# W101B.net
KiCad netlist of a schematic drawn in EAGLE
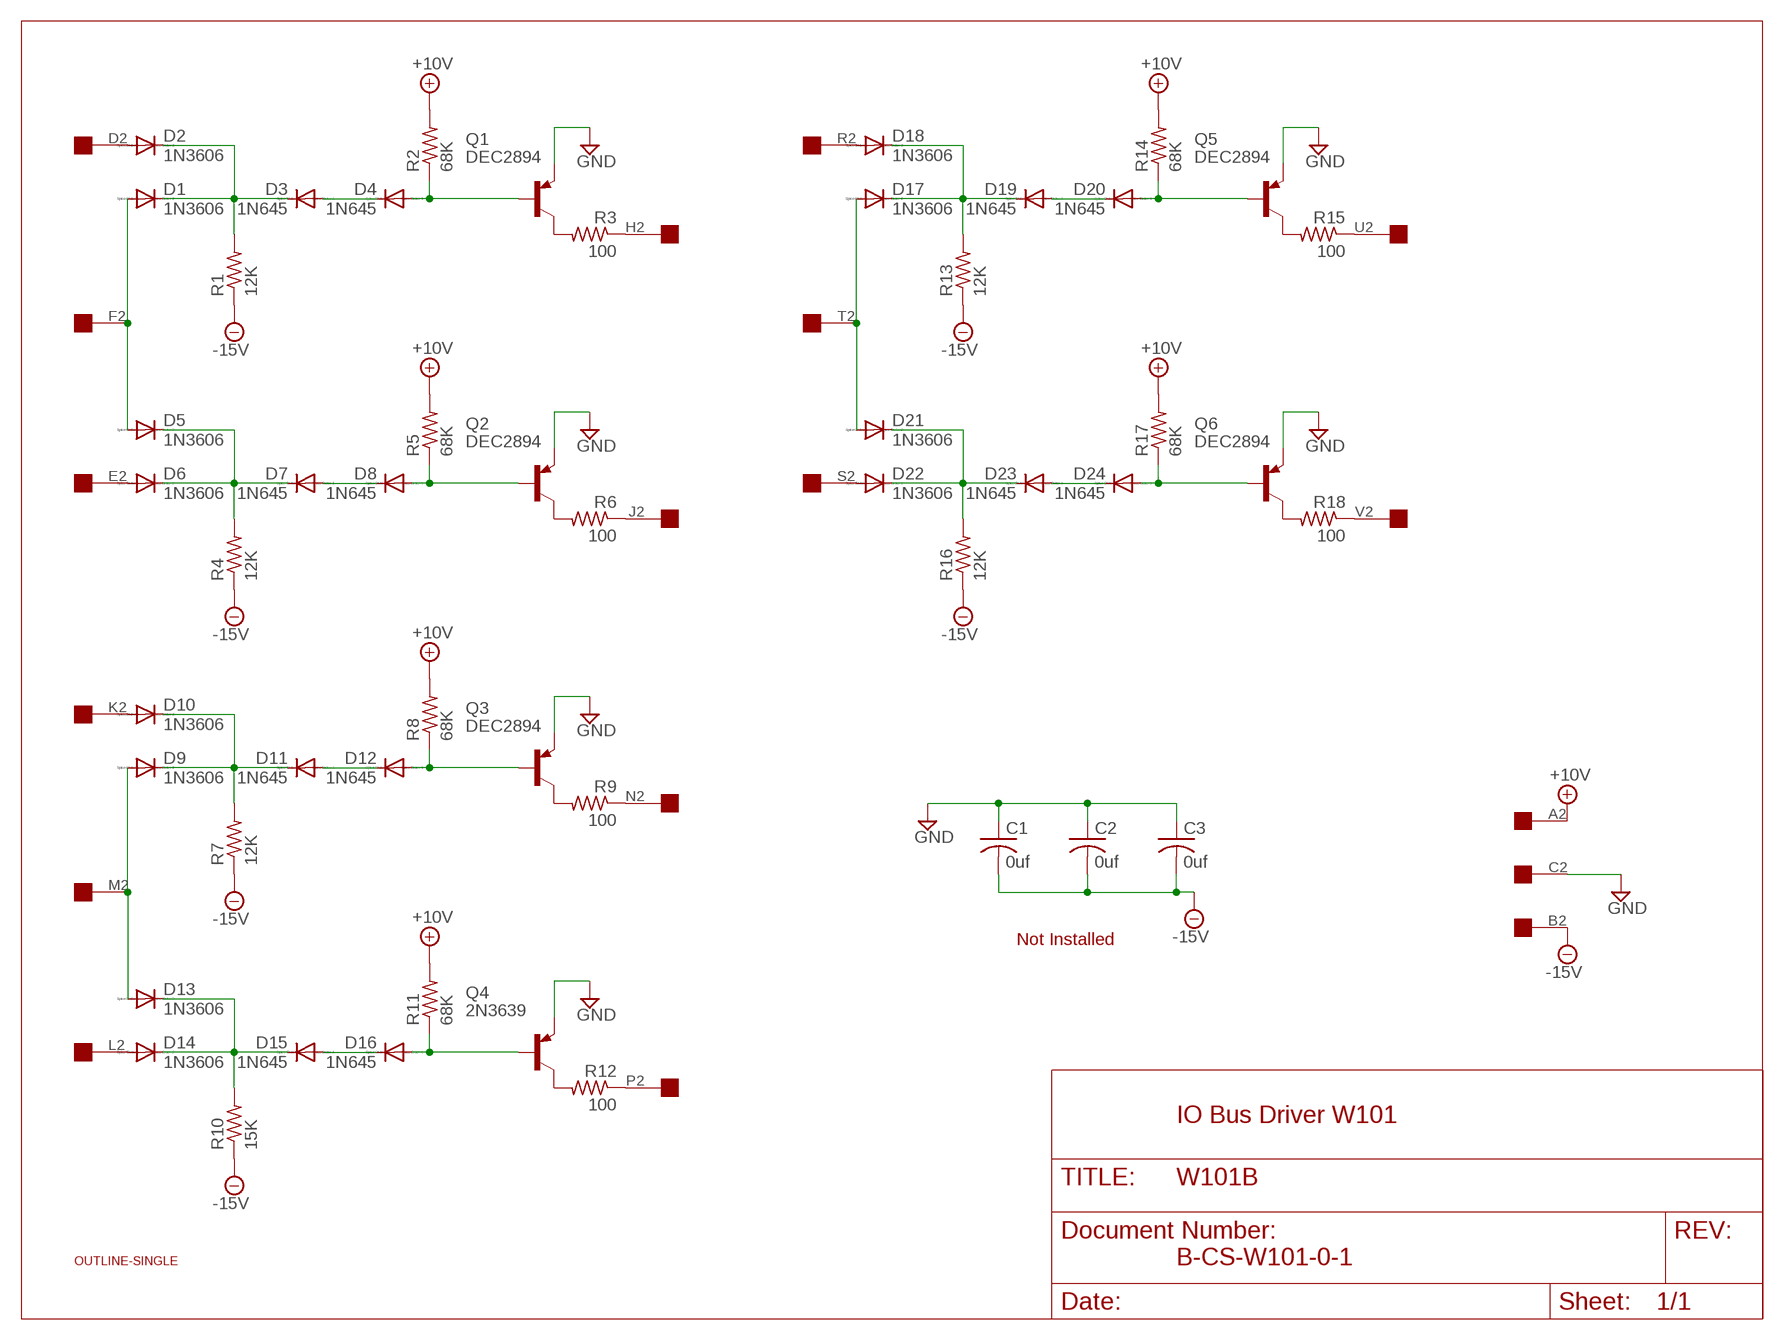
[diagram p0: schematic, sheet 1]

(export (version "E")
  (design (tool "Eeschema 10.0.6"))
  (components
    (comp (ref "C1")
      (value "0uf")
      (footprint "eagle-import:C050-025X075")
      (libsource (lib "eagle-import") (part "C-US050-025X075"))
    )
    (comp (ref "C2")
      (value "0uf")
      (footprint "eagle-import:C050-025X075")
      (libsource (lib "eagle-import") (part "C-US050-025X075"))
    )
    (comp (ref "C3")
      (value "0uf")
      (footprint "eagle-import:C050-025X075")
      (libsource (lib "eagle-import") (part "C-US050-025X075"))
    )
    (comp (ref "D1")
      (value "1N3606")
      (footprint "eagle-import:DO35-10")
      (libsource (lib "eagle-import") (part "1N4148DO35-10"))
    )
    (comp (ref "D2")
      (value "1N3606")
      (footprint "eagle-import:DO35-10")
      (libsource (lib "eagle-import") (part "1N4148DO35-10"))
    )
    (comp (ref "D3")
      (value "1N645")
      (footprint "eagle-import:DO35-10")
      (libsource (lib "eagle-import") (part "1N4148DO35-10"))
    )
    (comp (ref "D4")
      (value "1N645")
      (footprint "eagle-import:DO35-10")
      (libsource (lib "eagle-import") (part "1N4148DO35-10"))
    )
    (comp (ref "D5")
      (value "1N3606")
      (footprint "eagle-import:DO35-10")
      (libsource (lib "eagle-import") (part "1N4148DO35-10"))
    )
    (comp (ref "D6")
      (value "1N3606")
      (footprint "eagle-import:DO35-10")
      (libsource (lib "eagle-import") (part "1N4148DO35-10"))
    )
    (comp (ref "D7")
      (value "1N645")
      (footprint "eagle-import:DO35-10")
      (libsource (lib "eagle-import") (part "1N4148DO35-10"))
    )
    (comp (ref "D8")
      (value "1N645")
      (footprint "eagle-import:DO35-10")
      (libsource (lib "eagle-import") (part "1N4148DO35-10"))
    )
    (comp (ref "D9")
      (value "1N3606")
      (footprint "eagle-import:DO35-10")
      (libsource (lib "eagle-import") (part "1N4148DO35-10"))
    )
    (comp (ref "D10")
      (value "1N3606")
      (footprint "eagle-import:DO35-10")
      (libsource (lib "eagle-import") (part "1N4148DO35-10"))
    )
    (comp (ref "D11")
      (value "1N645")
      (footprint "eagle-import:DO35-10")
      (libsource (lib "eagle-import") (part "1N4148DO35-10"))
    )
    (comp (ref "D12")
      (value "1N645")
      (footprint "eagle-import:DO35-10")
      (libsource (lib "eagle-import") (part "1N4148DO35-10"))
    )
    (comp (ref "D13")
      (value "1N3606")
      (footprint "eagle-import:DO35-10")
      (libsource (lib "eagle-import") (part "1N4148DO35-10"))
    )
    (comp (ref "D14")
      (value "1N3606")
      (footprint "eagle-import:DO35-10")
      (libsource (lib "eagle-import") (part "1N4148DO35-10"))
    )
    (comp (ref "D15")
      (value "1N645")
      (footprint "eagle-import:DO35-10")
      (libsource (lib "eagle-import") (part "1N4148DO35-10"))
    )
    (comp (ref "D16")
      (value "1N645")
      (footprint "eagle-import:DO35-10")
      (libsource (lib "eagle-import") (part "1N4148DO35-10"))
    )
    (comp (ref "D17")
      (value "1N3606")
      (footprint "eagle-import:DO35-10")
      (libsource (lib "eagle-import") (part "1N4148DO35-10"))
    )
    (comp (ref "D18")
      (value "1N3606")
      (footprint "eagle-import:DO35-10")
      (libsource (lib "eagle-import") (part "1N4148DO35-10"))
    )
    (comp (ref "D19")
      (value "1N645")
      (footprint "eagle-import:DO35-10")
      (libsource (lib "eagle-import") (part "1N4148DO35-10"))
    )
    (comp (ref "D20")
      (value "1N645")
      (footprint "eagle-import:DO35-10")
      (libsource (lib "eagle-import") (part "1N4148DO35-10"))
    )
    (comp (ref "D21")
      (value "1N3606")
      (footprint "eagle-import:DO35-10")
      (libsource (lib "eagle-import") (part "1N4148DO35-10"))
    )
    (comp (ref "D22")
      (value "1N3606")
      (footprint "eagle-import:DO35-10")
      (libsource (lib "eagle-import") (part "1N4148DO35-10"))
    )
    (comp (ref "D23")
      (value "1N645")
      (footprint "eagle-import:DO35-10")
      (libsource (lib "eagle-import") (part "1N4148DO35-10"))
    )
    (comp (ref "D24")
      (value "1N645")
      (footprint "eagle-import:DO35-10")
      (libsource (lib "eagle-import") (part "1N4148DO35-10"))
    )
    (comp (ref "Q1")
      (value "DEC2894")
      (footprint "eagle-import:TO39")
      (libsource (lib "eagle-import") (part "2N3637"))
    )
    (comp (ref "Q2")
      (value "DEC2894")
      (footprint "eagle-import:TO39")
      (libsource (lib "eagle-import") (part "2N3637"))
    )
    (comp (ref "Q3")
      (value "DEC2894")
      (footprint "eagle-import:TO39")
      (libsource (lib "eagle-import") (part "2N3637"))
    )
    (comp (ref "Q4")
      (value "2N3639")
      (footprint "eagle-import:TO39")
      (libsource (lib "eagle-import") (part "2N3637"))
    )
    (comp (ref "Q5")
      (value "DEC2894")
      (footprint "eagle-import:TO39")
      (libsource (lib "eagle-import") (part "2N3637"))
    )
    (comp (ref "Q6")
      (value "DEC2894")
      (footprint "eagle-import:TO39")
      (libsource (lib "eagle-import") (part "2N3637"))
    )
    (comp (ref "R1")
      (value "12K")
      (footprint "eagle-import:0207_10")
      (libsource (lib "eagle-import") (part "R-US_0207/10"))
    )
    (comp (ref "R2")
      (value "68K")
      (footprint "eagle-import:0207_10")
      (libsource (lib "eagle-import") (part "R-US_0207/10"))
    )
    (comp (ref "R3")
      (value "100")
      (footprint "eagle-import:0207_10")
      (libsource (lib "eagle-import") (part "R-US_0207/10"))
    )
    (comp (ref "R4")
      (value "12K")
      (footprint "eagle-import:0207_10")
      (libsource (lib "eagle-import") (part "R-US_0207/10"))
    )
    (comp (ref "R5")
      (value "68K")
      (footprint "eagle-import:0207_10")
      (libsource (lib "eagle-import") (part "R-US_0207/10"))
    )
    (comp (ref "R6")
      (value "100")
      (footprint "eagle-import:0207_10")
      (libsource (lib "eagle-import") (part "R-US_0207/10"))
    )
    (comp (ref "R7")
      (value "12K")
      (footprint "eagle-import:0207_10")
      (libsource (lib "eagle-import") (part "R-US_0207/10"))
    )
    (comp (ref "R8")
      (value "68K")
      (footprint "eagle-import:0207_10")
      (libsource (lib "eagle-import") (part "R-US_0207/10"))
    )
    (comp (ref "R9")
      (value "100")
      (footprint "eagle-import:0207_10")
      (libsource (lib "eagle-import") (part "R-US_0207/10"))
    )
    (comp (ref "R10")
      (value "15K")
      (footprint "eagle-import:0207_10")
      (libsource (lib "eagle-import") (part "R-US_0207/10"))
    )
    (comp (ref "R11")
      (value "68K")
      (footprint "eagle-import:0207_10")
      (libsource (lib "eagle-import") (part "R-US_0207/10"))
    )
    (comp (ref "R12")
      (value "100")
      (footprint "eagle-import:0207_10")
      (libsource (lib "eagle-import") (part "R-US_0207/10"))
    )
    (comp (ref "R13")
      (value "12K")
      (footprint "eagle-import:0207_10")
      (libsource (lib "eagle-import") (part "R-US_0207/10"))
    )
    (comp (ref "R14")
      (value "68K")
      (footprint "eagle-import:0207_10")
      (libsource (lib "eagle-import") (part "R-US_0207/10"))
    )
    (comp (ref "R15")
      (value "100")
      (footprint "eagle-import:0207_10")
      (libsource (lib "eagle-import") (part "R-US_0207/10"))
    )
    (comp (ref "R16")
      (value "12K")
      (footprint "eagle-import:0207_10")
      (libsource (lib "eagle-import") (part "R-US_0207/10"))
    )
    (comp (ref "R17")
      (value "68K")
      (footprint "eagle-import:0207_10")
      (libsource (lib "eagle-import") (part "R-US_0207/10"))
    )
    (comp (ref "R18")
      (value "100")
      (footprint "eagle-import:0207_10")
      (libsource (lib "eagle-import") (part "R-US_0207/10"))
    )
    (comp (ref "U$1")
      (value "OUTLINE-SINGLE")
      (footprint "eagle-import:SINGLE")
      (libsource (lib "eagle-import") (part "OUTLINE-SINGLE"))
    )
    (comp (ref "U$2")
      (value "EDGE-1")
      (footprint "eagle-import:EDGE-CON1")
      (libsource (lib "eagle-import") (part "EDGE-1"))
    )
  )
  (nets
    (net (code "1") (name "+10V") (class "Default")
      (node (ref "R11") (pin "2") (pinfunction "2_2") (pintype "passive"))
      (node (ref "R14") (pin "2") (pinfunction "2_2") (pintype "passive"))
      (node (ref "R17") (pin "2") (pinfunction "2_2") (pintype "passive"))
      (node (ref "R2") (pin "2") (pinfunction "2_2") (pintype "passive"))
      (node (ref "R5") (pin "2") (pinfunction "2_2") (pintype "passive"))
      (node (ref "R8") (pin "2") (pinfunction "2_2") (pintype "passive"))
      (node (ref "U$2") (pin "A2") (pinfunction "1_A2") (pintype "bidirectional"))
    )
    (net (code "2") (name "-15V") (class "Default")
      (node (ref "C1") (pin "2") (pinfunction "2_2") (pintype "passive"))
      (node (ref "C2") (pin "2") (pinfunction "2_2") (pintype "passive"))
      (node (ref "C3") (pin "2") (pinfunction "2_2") (pintype "passive"))
      (node (ref "R1") (pin "1") (pinfunction "1_1") (pintype "passive"))
      (node (ref "R10") (pin "1") (pinfunction "1_1") (pintype "passive"))
      (node (ref "R13") (pin "1") (pinfunction "1_1") (pintype "passive"))
      (node (ref "R16") (pin "1") (pinfunction "1_1") (pintype "passive"))
      (node (ref "R4") (pin "1") (pinfunction "1_1") (pintype "passive"))
      (node (ref "R7") (pin "1") (pinfunction "1_1") (pintype "passive"))
      (node (ref "U$2") (pin "B2") (pinfunction "1_B2") (pintype "bidirectional"))
    )
    (net (code "3") (name "GND") (class "Default")
      (node (ref "C1") (pin "1") (pinfunction "1_1") (pintype "passive"))
      (node (ref "C2") (pin "1") (pinfunction "1_1") (pintype "passive"))
      (node (ref "C3") (pin "1") (pinfunction "1_1") (pintype "passive"))
      (node (ref "Q1") (pin "1") (pinfunction "E_1") (pintype "passive"))
      (node (ref "Q2") (pin "1") (pinfunction "E_1") (pintype "passive"))
      (node (ref "Q3") (pin "1") (pinfunction "E_1") (pintype "passive"))
      (node (ref "Q4") (pin "1") (pinfunction "E_1") (pintype "passive"))
      (node (ref "Q5") (pin "1") (pinfunction "E_1") (pintype "passive"))
      (node (ref "Q6") (pin "1") (pinfunction "E_1") (pintype "passive"))
      (node (ref "U$2") (pin "C2") (pinfunction "1_C2") (pintype "bidirectional"))
    )
    (net (code "4") (name "Net-(D1-PadC)") (class "Default")
      (node (ref "D1") (pin "C") (pinfunction "C_C") (pintype "passive"))
      (node (ref "D2") (pin "C") (pinfunction "C_C") (pintype "passive"))
      (node (ref "D3") (pin "C") (pinfunction "C_C") (pintype "passive"))
      (node (ref "R1") (pin "2") (pinfunction "2_2") (pintype "passive"))
    )
    (net (code "5") (name "Net-(D3-PadA)") (class "Default")
      (node (ref "D3") (pin "A") (pinfunction "A_A") (pintype "passive"))
      (node (ref "D4") (pin "C") (pinfunction "C_C") (pintype "passive"))
    )
    (net (code "6") (name "Net-(D5-PadC)") (class "Default")
      (node (ref "D5") (pin "C") (pinfunction "C_C") (pintype "passive"))
      (node (ref "D6") (pin "C") (pinfunction "C_C") (pintype "passive"))
      (node (ref "D7") (pin "C") (pinfunction "C_C") (pintype "passive"))
      (node (ref "R4") (pin "2") (pinfunction "2_2") (pintype "passive"))
    )
    (net (code "7") (name "Net-(D7-PadA)") (class "Default")
      (node (ref "D7") (pin "A") (pinfunction "A_A") (pintype "passive"))
      (node (ref "D8") (pin "C") (pinfunction "C_C") (pintype "passive"))
    )
    (net (code "8") (name "Net-(D10-PadC)") (class "Default")
      (node (ref "D10") (pin "C") (pinfunction "C_C") (pintype "passive"))
      (node (ref "D11") (pin "C") (pinfunction "C_C") (pintype "passive"))
      (node (ref "D9") (pin "C") (pinfunction "C_C") (pintype "passive"))
      (node (ref "R7") (pin "2") (pinfunction "2_2") (pintype "passive"))
    )
    (net (code "9") (name "Net-(D11-PadA)") (class "Default")
      (node (ref "D11") (pin "A") (pinfunction "A_A") (pintype "passive"))
      (node (ref "D12") (pin "C") (pinfunction "C_C") (pintype "passive"))
    )
    (net (code "10") (name "Net-(D13-PadC)") (class "Default")
      (node (ref "D13") (pin "C") (pinfunction "C_C") (pintype "passive"))
      (node (ref "D14") (pin "C") (pinfunction "C_C") (pintype "passive"))
      (node (ref "D15") (pin "C") (pinfunction "C_C") (pintype "passive"))
      (node (ref "R10") (pin "2") (pinfunction "2_2") (pintype "passive"))
    )
    (net (code "11") (name "Net-(D15-PadA)") (class "Default")
      (node (ref "D15") (pin "A") (pinfunction "A_A") (pintype "passive"))
      (node (ref "D16") (pin "C") (pinfunction "C_C") (pintype "passive"))
    )
    (net (code "12") (name "Net-(D17-PadC)") (class "Default")
      (node (ref "D17") (pin "C") (pinfunction "C_C") (pintype "passive"))
      (node (ref "D18") (pin "C") (pinfunction "C_C") (pintype "passive"))
      (node (ref "D19") (pin "C") (pinfunction "C_C") (pintype "passive"))
      (node (ref "R13") (pin "2") (pinfunction "2_2") (pintype "passive"))
    )
    (net (code "13") (name "Net-(D19-PadA)") (class "Default")
      (node (ref "D19") (pin "A") (pinfunction "A_A") (pintype "passive"))
      (node (ref "D20") (pin "C") (pinfunction "C_C") (pintype "passive"))
    )
    (net (code "14") (name "Net-(D21-PadC)") (class "Default")
      (node (ref "D21") (pin "C") (pinfunction "C_C") (pintype "passive"))
      (node (ref "D22") (pin "C") (pinfunction "C_C") (pintype "passive"))
      (node (ref "D23") (pin "C") (pinfunction "C_C") (pintype "passive"))
      (node (ref "R16") (pin "2") (pinfunction "2_2") (pintype "passive"))
    )
    (net (code "15") (name "Net-(D23-PadA)") (class "Default")
      (node (ref "D23") (pin "A") (pinfunction "A_A") (pintype "passive"))
      (node (ref "D24") (pin "C") (pinfunction "C_C") (pintype "passive"))
    )
    (net (code "16") (name "Net-(Q1-B)") (class "Default")
      (node (ref "D4") (pin "A") (pinfunction "A_A") (pintype "passive"))
      (node (ref "Q1") (pin "2") (pinfunction "B_2") (pintype "passive"))
      (node (ref "R2") (pin "1") (pinfunction "1_1") (pintype "passive"))
    )
    (net (code "17") (name "Net-(Q1-C)") (class "Default")
      (node (ref "Q1") (pin "3") (pinfunction "C_3") (pintype "passive"))
      (node (ref "R3") (pin "2") (pinfunction "2_2") (pintype "passive"))
    )
    (net (code "18") (name "Net-(Q2-B)") (class "Default")
      (node (ref "D8") (pin "A") (pinfunction "A_A") (pintype "passive"))
      (node (ref "Q2") (pin "2") (pinfunction "B_2") (pintype "passive"))
      (node (ref "R5") (pin "1") (pinfunction "1_1") (pintype "passive"))
    )
    (net (code "19") (name "Net-(Q2-C)") (class "Default")
      (node (ref "Q2") (pin "3") (pinfunction "C_3") (pintype "passive"))
      (node (ref "R6") (pin "2") (pinfunction "2_2") (pintype "passive"))
    )
    (net (code "20") (name "Net-(Q3-B)") (class "Default")
      (node (ref "D12") (pin "A") (pinfunction "A_A") (pintype "passive"))
      (node (ref "Q3") (pin "2") (pinfunction "B_2") (pintype "passive"))
      (node (ref "R8") (pin "1") (pinfunction "1_1") (pintype "passive"))
    )
    (net (code "21") (name "Net-(Q3-C)") (class "Default")
      (node (ref "Q3") (pin "3") (pinfunction "C_3") (pintype "passive"))
      (node (ref "R9") (pin "2") (pinfunction "2_2") (pintype "passive"))
    )
    (net (code "22") (name "Net-(Q4-B)") (class "Default")
      (node (ref "D16") (pin "A") (pinfunction "A_A") (pintype "passive"))
      (node (ref "Q4") (pin "2") (pinfunction "B_2") (pintype "passive"))
      (node (ref "R11") (pin "1") (pinfunction "1_1") (pintype "passive"))
    )
    (net (code "23") (name "Net-(Q4-C)") (class "Default")
      (node (ref "Q4") (pin "3") (pinfunction "C_3") (pintype "passive"))
      (node (ref "R12") (pin "2") (pinfunction "2_2") (pintype "passive"))
    )
    (net (code "24") (name "Net-(Q5-B)") (class "Default")
      (node (ref "D20") (pin "A") (pinfunction "A_A") (pintype "passive"))
      (node (ref "Q5") (pin "2") (pinfunction "B_2") (pintype "passive"))
      (node (ref "R14") (pin "1") (pinfunction "1_1") (pintype "passive"))
    )
    (net (code "25") (name "Net-(Q5-C)") (class "Default")
      (node (ref "Q5") (pin "3") (pinfunction "C_3") (pintype "passive"))
      (node (ref "R15") (pin "2") (pinfunction "2_2") (pintype "passive"))
    )
    (net (code "26") (name "Net-(Q6-B)") (class "Default")
      (node (ref "D24") (pin "A") (pinfunction "A_A") (pintype "passive"))
      (node (ref "Q6") (pin "2") (pinfunction "B_2") (pintype "passive"))
      (node (ref "R17") (pin "1") (pinfunction "1_1") (pintype "passive"))
    )
    (net (code "27") (name "Net-(Q6-C)") (class "Default")
      (node (ref "Q6") (pin "3") (pinfunction "C_3") (pintype "passive"))
      (node (ref "R18") (pin "2") (pinfunction "2_2") (pintype "passive"))
    )
    (net (code "28") (name "Net-(U$2D-1)") (class "Default")
      (node (ref "D2") (pin "A") (pinfunction "A_A") (pintype "passive"))
      (node (ref "U$2") (pin "D2") (pinfunction "1_D2") (pintype "bidirectional"))
    )
    (net (code "29") (name "Net-(U$2E-1)") (class "Default")
      (node (ref "D6") (pin "A") (pinfunction "A_A") (pintype "passive"))
      (node (ref "U$2") (pin "E2") (pinfunction "1_E2") (pintype "bidirectional"))
    )
    (net (code "30") (name "Net-(U$2F-1)") (class "Default")
      (node (ref "D1") (pin "A") (pinfunction "A_A") (pintype "passive"))
      (node (ref "D5") (pin "A") (pinfunction "A_A") (pintype "passive"))
      (node (ref "U$2") (pin "F2") (pinfunction "1_F2") (pintype "bidirectional"))
    )
    (net (code "31") (name "Net-(U$2G-1)") (class "Default")
      (node (ref "R3") (pin "1") (pinfunction "1_1") (pintype "passive"))
      (node (ref "U$2") (pin "H2") (pinfunction "1_H2") (pintype "bidirectional"))
    )
    (net (code "32") (name "Net-(U$2H-1)") (class "Default")
      (node (ref "R6") (pin "1") (pinfunction "1_1") (pintype "passive"))
      (node (ref "U$2") (pin "J2") (pinfunction "1_J2") (pintype "bidirectional"))
    )
    (net (code "33") (name "Net-(U$2I-1)") (class "Default")
      (node (ref "D10") (pin "A") (pinfunction "A_A") (pintype "passive"))
      (node (ref "U$2") (pin "K2") (pinfunction "1_K2") (pintype "bidirectional"))
    )
    (net (code "34") (name "Net-(U$2J-1)") (class "Default")
      (node (ref "D14") (pin "A") (pinfunction "A_A") (pintype "passive"))
      (node (ref "U$2") (pin "L2") (pinfunction "1_L2") (pintype "bidirectional"))
    )
    (net (code "35") (name "Net-(U$2K-1)") (class "Default")
      (node (ref "D13") (pin "A") (pinfunction "A_A") (pintype "passive"))
      (node (ref "D9") (pin "A") (pinfunction "A_A") (pintype "passive"))
      (node (ref "U$2") (pin "M2") (pinfunction "1_M2") (pintype "bidirectional"))
    )
    (net (code "36") (name "Net-(U$2L-1)") (class "Default")
      (node (ref "R9") (pin "1") (pinfunction "1_1") (pintype "passive"))
      (node (ref "U$2") (pin "N2") (pinfunction "1_N2") (pintype "bidirectional"))
    )
    (net (code "37") (name "Net-(U$2M-1)") (class "Default")
      (node (ref "R12") (pin "1") (pinfunction "1_1") (pintype "passive"))
      (node (ref "U$2") (pin "P2") (pinfunction "1_P2") (pintype "bidirectional"))
    )
    (net (code "38") (name "Net-(U$2N-1)") (class "Default")
      (node (ref "D18") (pin "A") (pinfunction "A_A") (pintype "passive"))
      (node (ref "U$2") (pin "R2") (pinfunction "1_R2") (pintype "bidirectional"))
    )
    (net (code "39") (name "Net-(U$2O-1)") (class "Default")
      (node (ref "D22") (pin "A") (pinfunction "A_A") (pintype "passive"))
      (node (ref "U$2") (pin "S2") (pinfunction "1_S2") (pintype "bidirectional"))
    )
    (net (code "40") (name "Net-(U$2P-1)") (class "Default")
      (node (ref "D17") (pin "A") (pinfunction "A_A") (pintype "passive"))
      (node (ref "D21") (pin "A") (pinfunction "A_A") (pintype "passive"))
      (node (ref "U$2") (pin "T2") (pinfunction "1_T2") (pintype "bidirectional"))
    )
    (net (code "41") (name "Net-(U$2Q-1)") (class "Default")
      (node (ref "R15") (pin "1") (pinfunction "1_1") (pintype "passive"))
      (node (ref "U$2") (pin "U2") (pinfunction "1_U2") (pintype "bidirectional"))
    )
    (net (code "42") (name "Net-(U$2R-1)") (class "Default")
      (node (ref "R18") (pin "1") (pinfunction "1_1") (pintype "passive"))
      (node (ref "U$2") (pin "V2") (pinfunction "1_V2") (pintype "bidirectional"))
    )
  )
)
